# Flash.net
KiCad netlist of a schematic drawn in Altium Designer
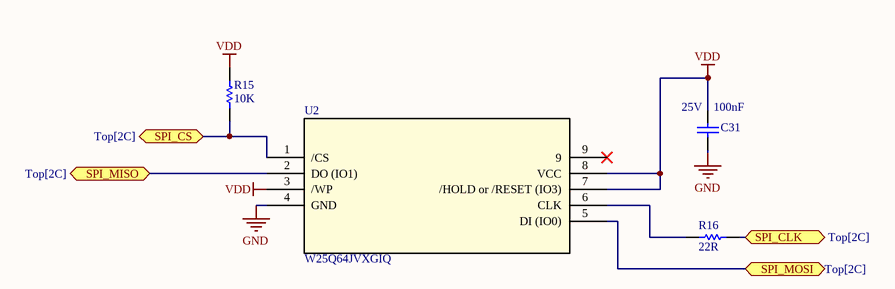
[diagram p0: Flash.SchDoc]

(export (version "E")
  (design (tool "Eeschema 10.0.6"))
  (components
    (comp (ref "C31")
      (value "100nF")
      (footprint "C0402")
      (description "Multilayer Ceramic Capacitors MLCC - SMD/SMT 0402 0.10uF 25volt X5R +/-10%")
      (fields
        (field (name "MANUFACTURER") "Murata")
        (field (name "MANUFACTURER PART NUMBER") "GRM155R61E104KA87D")
        (field (name "VOLTAGE RATING (DC)") "25V")
      )
      (libsource (lib "MCD_PARTS_database") (part "Capacitor"))
    )
    (comp (ref "R15")
      (value "10K")
      (footprint "R0402")
      (description "Resistor, 10K, 0402, +/-0.1%, 1/16W, +/-25ppm/°C")
      (fields (field (name "INTERNAL_PART_NUMBER") "MCD-02551") (field (name "MANUFACTURER") "YAGEO"))
      (libsource (lib "MCD_PARTS_database") (part "Resistor"))
    )
    (comp (ref "R16")
      (value "22R")
      (footprint "R0402")
      (description "Resistor, 22R, 0402, +/-1%, 1/16W")
      (fields (field (name "INTERNAL_PART_NUMBER") "MCD-00189") (field (name "MANUFACTURER") "YAGEO"))
      (libsource (lib "MCD_PARTS_database") (part "Resistor"))
    )
    (comp (ref "U2")
      (value "W25Q64JVXGIQ")
      (footprint "DFN_XGIQ TR_WIN-L")
      (description "64Mb Serial NOR Flash 133MHz XSON8")
      (fields
        (field (name "MANUFACTURER_PART_NUMBER") "W25Q64JVXGIQ TR")
        (field (name "MANUFACTURER") "Winbond")
        (field (name "COPYRIGHT") "Copyright (C) 2023 Ultra Librarian. All rights reserved.")
      )
      (libsource (lib "STEVAL-ESLBLECB") (part "W25Q64JVXGIQ TR"))
    )
  )
  (nets
    (net (code "1") (name "/SPI_CLK") (class "Default")
      (node (ref "R16") (pin "1") (pinfunction "1_1") (pintype "passive"))
    )
    (net (code "2") (name "/SPI_CS") (class "Default")
      (node (ref "R15") (pin "1") (pinfunction "1_1") (pintype "passive"))
      (node (ref "U2") (pin "1") (pinfunction "/CS_1") (pintype "passive"))
    )
    (net (code "3") (name "/SPI_MISO") (class "Default")
      (node (ref "U2") (pin "2") (pinfunction "DO_(IO1)_2") (pintype "passive"))
    )
    (net (code "4") (name "/SPI_MOSI") (class "Default")
      (node (ref "U2") (pin "5") (pinfunction "DI_(IO0)_5") (pintype "passive"))
    )
    (net (code "5") (name "GND") (class "Default")
      (node (ref "C31") (pin "1") (pinfunction "1_1") (pintype "passive"))
      (node (ref "U2") (pin "4") (pinfunction "GND_4") (pintype "power_in"))
    )
    (net (code "6") (name "Net-(U2-CLK)") (class "Default")
      (node (ref "R16") (pin "2") (pinfunction "2_2") (pintype "passive"))
      (node (ref "U2") (pin "6") (pinfunction "CLK_6") (pintype "passive"))
    )
    (net (code "7") (name "VDD") (class "Default")
      (node (ref "C31") (pin "2") (pinfunction "2_2") (pintype "passive"))
      (node (ref "R15") (pin "2") (pinfunction "2_2") (pintype "passive"))
      (node (ref "U2") (pin "3") (pinfunction "/WP_3") (pintype "passive"))
      (node (ref "U2") (pin "7") (pinfunction "/HOLD_or_/RESET_(IO3)_7") (pintype "passive"))
      (node (ref "U2") (pin "8") (pinfunction "VCC_8") (pintype "power_in"))
    )
    (net (code "8") (name "unconnected-(U2-Pad9)") (class "Default")
      (node (ref "U2") (pin "9") (pinfunction "9_9") (pintype "passive+no_connect"))
    )
  )
)
